# Base_Station_2_4.net
KiCad netlist of a schematic drawn in EAGLE
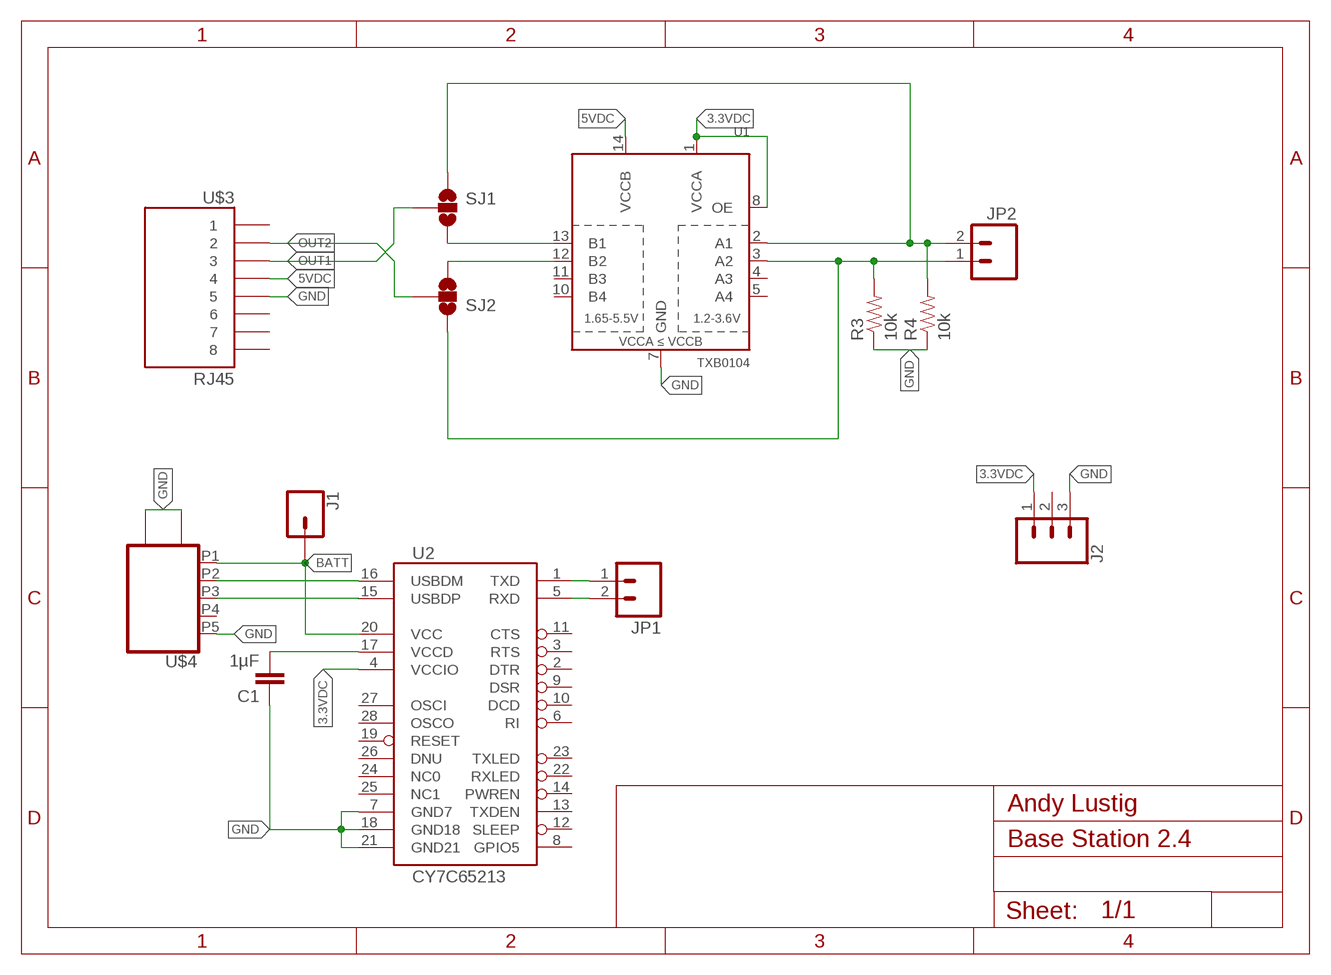
[diagram p0: schematic, sheet 1]

(export (version "E")
  (design (tool "Eeschema 10.0.6"))
  (components
    (comp (ref "C1")
      (value "1µF")
      (footprint "eagle-import:0603")
      (libsource (lib "eagle-import") (part "0.1UF-0603-25V-5%"))
    )
    (comp (ref "J1")
      (value "CONN_01PTH_NO_SILK_YES_STOP")
      (footprint "eagle-import:1X01_NO_SILK")
      (libsource (lib "eagle-import") (part "CONN_01PTH_NO_SILK_YES_STOP"))
    )
    (comp (ref "J2")
      (value "CONN_031X03_NO_SILK")
      (footprint "eagle-import:1X03_NO_SILK")
      (libsource (lib "eagle-import") (part "CONN_031X03_NO_SILK"))
    )
    (comp (ref "JP1")
      (value "M021X02_NO_SILK")
      (footprint "eagle-import:1X02_NO_SILK")
      (libsource (lib "eagle-import") (part "M021X02_NO_SILK"))
    )
    (comp (ref "JP2")
      (value "M021X02_NO_SILK")
      (footprint "eagle-import:1X02_NO_SILK")
      (libsource (lib "eagle-import") (part "M021X02_NO_SILK"))
    )
    (comp (ref "R3")
      (value "10k")
      (footprint "eagle-import:0805")
      (libsource (lib "eagle-import") (part "RESISTOR0805-RES"))
    )
    (comp (ref "R4")
      (value "10k")
      (footprint "eagle-import:0805")
      (libsource (lib "eagle-import") (part "RESISTOR0805-RES"))
    )
    (comp (ref "SJ1")
      (value "SOLDERJUMPER_2WAYPASTE2&3")
      (footprint "eagle-import:SJ_3_PASTE2&3")
      (libsource (lib "eagle-import") (part "SOLDERJUMPER_2WAYPASTE2&3"))
    )
    (comp (ref "SJ2")
      (value "SOLDERJUMPER_2WAYPASTE2&3")
      (footprint "eagle-import:SJ_3_PASTE2&3")
      (libsource (lib "eagle-import") (part "SOLDERJUMPER_2WAYPASTE2&3"))
    )
    (comp (ref "U$3")
      (value "RJ45")
      (footprint "eagle-import:RJ45-8")
      (libsource (lib "eagle-import") (part "RJ45"))
    )
    (comp (ref "U$4")
      (value "USB_MICRO_SOCKET_HORZ_REINFORCED")
      (footprint "eagle-import:USB_HORZ_REINFORCED_MICRO")
      (libsource (lib "eagle-import") (part "USB_MICRO_SOCKET_HORZ_REINFORCED"))
    )
    (comp (ref "U1")
      (value "TXB0104")
      (footprint "eagle-import:TSSOP14")
      (libsource (lib "eagle-import") (part "TXB0104PWR"))
    )
    (comp (ref "U2")
      (value "CY7C65213")
      (footprint "eagle-import:SSOP28DB")
      (libsource (lib "eagle-import") (part "CY7C65213"))
    )
  )
  (nets
    (net (code "1") (name "/NC1") (class "Default")
      (node (ref "U2") (pin "25") (pinfunction "NC1_25") (pintype "power_in"))
    )
    (net (code "2") (name "3.3VDC") (class "Default")
      (node (ref "J2") (pin "1") (pinfunction "1_1") (pintype "passive"))
      (node (ref "U1") (pin "1") (pinfunction "VCCA_1") (pintype "bidirectional"))
      (node (ref "U1") (pin "8") (pinfunction "OE_8") (pintype "bidirectional"))
      (node (ref "U2") (pin "4") (pinfunction "VCCIO_4") (pintype "power_in"))
    )
    (net (code "3") (name "5VDC") (class "Default")
      (node (ref "U$3") (pin "4") (pinfunction "4_4") (pintype "bidirectional"))
      (node (ref "U1") (pin "14") (pinfunction "VCCB_14") (pintype "bidirectional"))
    )
    (net (code "4") (name "BATT") (class "Default")
      (node (ref "J1") (pin "1") (pinfunction "1_1") (pintype "passive"))
      (node (ref "U$4") (pin "P1") (pinfunction "P1_P1") (pintype "bidirectional"))
      (node (ref "U2") (pin "20") (pinfunction "VCC_20") (pintype "power_in"))
    )
    (net (code "5") (name "GND") (class "Default")
      (node (ref "C1") (pin "1") (pinfunction "1_1") (pintype "passive"))
      (node (ref "J2") (pin "3") (pinfunction "3_3") (pintype "passive"))
      (node (ref "R3") (pin "1") (pinfunction "1_1") (pintype "passive"))
      (node (ref "R4") (pin "1") (pinfunction "1_1") (pintype "passive"))
      (node (ref "U$3") (pin "5") (pinfunction "5_5") (pintype "bidirectional"))
      (node (ref "U$4") (pin "G1") (pinfunction "P$1_G1") (pintype "bidirectional"))
      (node (ref "U$4") (pin "G2") (pinfunction "P$1_G2") (pintype "bidirectional"))
      (node (ref "U$4") (pin "P$1") (pinfunction "P$2_P$1") (pintype "bidirectional"))
      (node (ref "U$4") (pin "P$2") (pinfunction "P$2_P$2") (pintype "bidirectional"))
      (node (ref "U$4") (pin "P5") (pinfunction "P5_P5") (pintype "bidirectional"))
      (node (ref "U1") (pin "7") (pinfunction "GND_7") (pintype "bidirectional"))
      (node (ref "U2") (pin "18") (pinfunction "GND18_18") (pintype "power_in"))
      (node (ref "U2") (pin "21") (pinfunction "GND21_21") (pintype "power_in"))
      (node (ref "U2") (pin "7") (pinfunction "GND7_7") (pintype "power_in"))
    )
    (net (code "6") (name "Net-(U1-A1)") (class "Default")
      (node (ref "JP2") (pin "2") (pinfunction "2_2") (pintype "passive"))
      (node (ref "R4") (pin "2") (pinfunction "2_2") (pintype "passive"))
      (node (ref "SJ1") (pin "1") (pinfunction "1_1") (pintype "passive"))
      (node (ref "U1") (pin "2") (pinfunction "A1_2") (pintype "bidirectional"))
    )
    (net (code "7") (name "Net-(U1-A2)") (class "Default")
      (node (ref "JP2") (pin "1") (pinfunction "1_1") (pintype "passive"))
      (node (ref "R3") (pin "2") (pinfunction "2_2") (pintype "passive"))
      (node (ref "SJ2") (pin "1") (pinfunction "1_1") (pintype "passive"))
      (node (ref "U1") (pin "3") (pinfunction "A2_3") (pintype "bidirectional"))
    )
    (net (code "8") (name "Net-(U1-B1)") (class "Default")
      (node (ref "SJ1") (pin "3") (pinfunction "3_3") (pintype "passive"))
      (node (ref "U1") (pin "13") (pinfunction "B1_13") (pintype "bidirectional"))
    )
    (net (code "9") (name "Net-(U1-B2)") (class "Default")
      (node (ref "SJ2") (pin "3") (pinfunction "3_3") (pintype "passive"))
      (node (ref "U1") (pin "12") (pinfunction "B2_12") (pintype "bidirectional"))
    )
    (net (code "10") (name "Net-(U2-RXD)") (class "Default")
      (node (ref "JP1") (pin "2") (pinfunction "2_2") (pintype "passive"))
      (node (ref "U2") (pin "5") (pinfunction "RXD_5") (pintype "input"))
    )
    (net (code "11") (name "Net-(U2-TXD)") (class "Default")
      (node (ref "JP1") (pin "1") (pinfunction "1_1") (pintype "passive"))
      (node (ref "U2") (pin "1") (pinfunction "TXD_1") (pintype "output"))
    )
    (net (code "12") (name "Net-(U2-USBDM)") (class "Default")
      (node (ref "U$4") (pin "P2") (pinfunction "P2_P2") (pintype "bidirectional"))
      (node (ref "U2") (pin "16") (pinfunction "USBDM_16") (pintype "bidirectional"))
    )
    (net (code "13") (name "Net-(U2-USBDP)") (class "Default")
      (node (ref "U$4") (pin "P3") (pinfunction "P3_P3") (pintype "bidirectional"))
      (node (ref "U2") (pin "15") (pinfunction "USBDP_15") (pintype "bidirectional"))
    )
    (net (code "14") (name "Net-(U2-VCCD)") (class "Default")
      (node (ref "C1") (pin "2") (pinfunction "2_2") (pintype "passive"))
      (node (ref "U2") (pin "17") (pinfunction "VCCD_17") (pintype "output"))
    )
    (net (code "15") (name "OUT1") (class "Default")
      (node (ref "SJ1") (pin "2") (pinfunction "2_2") (pintype "passive"))
      (node (ref "U$3") (pin "3") (pinfunction "3_3") (pintype "bidirectional"))
    )
    (net (code "16") (name "OUT2") (class "Default")
      (node (ref "SJ2") (pin "2") (pinfunction "2_2") (pintype "passive"))
      (node (ref "U$3") (pin "2") (pinfunction "2_2") (pintype "bidirectional"))
    )
    (net (code "17") (name "unconnected-(J2-Pad2)") (class "Default")
      (node (ref "J2") (pin "2") (pinfunction "2_2") (pintype "passive"))
    )
    (net (code "18") (name "unconnected-(U$3-Pad1)") (class "Default")
      (node (ref "U$3") (pin "1") (pinfunction "1_1") (pintype "bidirectional"))
    )
    (net (code "19") (name "unconnected-(U$3-Pad6)") (class "Default")
      (node (ref "U$3") (pin "6") (pinfunction "6_6") (pintype "bidirectional"))
    )
    (net (code "20") (name "unconnected-(U$3-Pad7)") (class "Default")
      (node (ref "U$3") (pin "7") (pinfunction "7_7") (pintype "bidirectional"))
    )
    (net (code "21") (name "unconnected-(U$3-Pad8)") (class "Default")
      (node (ref "U$3") (pin "8") (pinfunction "8_8") (pintype "bidirectional"))
    )
    (net (code "22") (name "unconnected-(U$4-PadP4)") (class "Default")
      (node (ref "U$4") (pin "P4") (pinfunction "P4_P4") (pintype "bidirectional"))
    )
    (net (code "23") (name "unconnected-(U1-A3-Pad4)") (class "Default")
      (node (ref "U1") (pin "4") (pinfunction "A3_4") (pintype "bidirectional"))
    )
    (net (code "24") (name "unconnected-(U1-A4-Pad5)") (class "Default")
      (node (ref "U1") (pin "5") (pinfunction "A4_5") (pintype "bidirectional"))
    )
    (net (code "25") (name "unconnected-(U1-B3-Pad11)") (class "Default")
      (node (ref "U1") (pin "11") (pinfunction "B3_11") (pintype "bidirectional"))
    )
    (net (code "26") (name "unconnected-(U1-B4-Pad10)") (class "Default")
      (node (ref "U1") (pin "10") (pinfunction "B4_10") (pintype "bidirectional"))
    )
    (net (code "27") (name "unconnected-(U2-CTS-Pad11)") (class "Default")
      (node (ref "U2") (pin "11") (pinfunction "CTS_11") (pintype "input"))
    )
    (net (code "28") (name "unconnected-(U2-DCD-Pad10)") (class "Default")
      (node (ref "U2") (pin "10") (pinfunction "DCD_10") (pintype "input"))
    )
    (net (code "29") (name "unconnected-(U2-DNU-Pad26)") (class "Default")
      (node (ref "U2") (pin "26") (pinfunction "DNU_26") (pintype "input"))
    )
    (net (code "30") (name "unconnected-(U2-DSR-Pad9)") (class "Default")
      (node (ref "U2") (pin "9") (pinfunction "DSR_9") (pintype "input"))
    )
    (net (code "31") (name "unconnected-(U2-DTR-Pad2)") (class "Default")
      (node (ref "U2") (pin "2") (pinfunction "DTR_2") (pintype "output"))
    )
    (net (code "32") (name "unconnected-(U2-GPIO5-Pad8)") (class "Default")
      (node (ref "U2") (pin "8") (pinfunction "GPIO5_8") (pintype "input"))
    )
    (net (code "33") (name "unconnected-(U2-NC0-Pad24)") (class "Default")
      (node (ref "U2") (pin "24") (pinfunction "NC0_24") (pintype "input"))
    )
    (net (code "34") (name "unconnected-(U2-OSCI-Pad27)") (class "Default")
      (node (ref "U2") (pin "27") (pinfunction "OSCI_27") (pintype "input"))
    )
    (net (code "35") (name "unconnected-(U2-OSCO-Pad28)") (class "Default")
      (node (ref "U2") (pin "28") (pinfunction "OSCO_28") (pintype "output"))
    )
    (net (code "36") (name "unconnected-(U2-PWREN-Pad14)") (class "Default")
      (node (ref "U2") (pin "14") (pinfunction "PWREN_14") (pintype "input"))
    )
    (net (code "37") (name "unconnected-(U2-RESET-Pad19)") (class "Default")
      (node (ref "U2") (pin "19") (pinfunction "RESET_19") (pintype "input"))
    )
    (net (code "38") (name "unconnected-(U2-RI-Pad6)") (class "Default")
      (node (ref "U2") (pin "6") (pinfunction "RI_6") (pintype "input"))
    )
    (net (code "39") (name "unconnected-(U2-RTS-Pad3)") (class "Default")
      (node (ref "U2") (pin "3") (pinfunction "RTS_3") (pintype "output"))
    )
    (net (code "40") (name "unconnected-(U2-RXLED-Pad22)") (class "Default")
      (node (ref "U2") (pin "22") (pinfunction "RXLED_22") (pintype "input"))
    )
    (net (code "41") (name "unconnected-(U2-SLEEP-Pad12)") (class "Default")
      (node (ref "U2") (pin "12") (pinfunction "SLEEP_12") (pintype "input"))
    )
    (net (code "42") (name "unconnected-(U2-TXDEN-Pad13)") (class "Default")
      (node (ref "U2") (pin "13") (pinfunction "TXDEN_13") (pintype "input"))
    )
    (net (code "43") (name "unconnected-(U2-TXLED-Pad23)") (class "Default")
      (node (ref "U2") (pin "23") (pinfunction "TXLED_23") (pintype "input"))
    )
  )
)
